# ProPrj_ESP_DigiCam.net
KiCad netlist of a schematic drawn in EasyEDA Pro
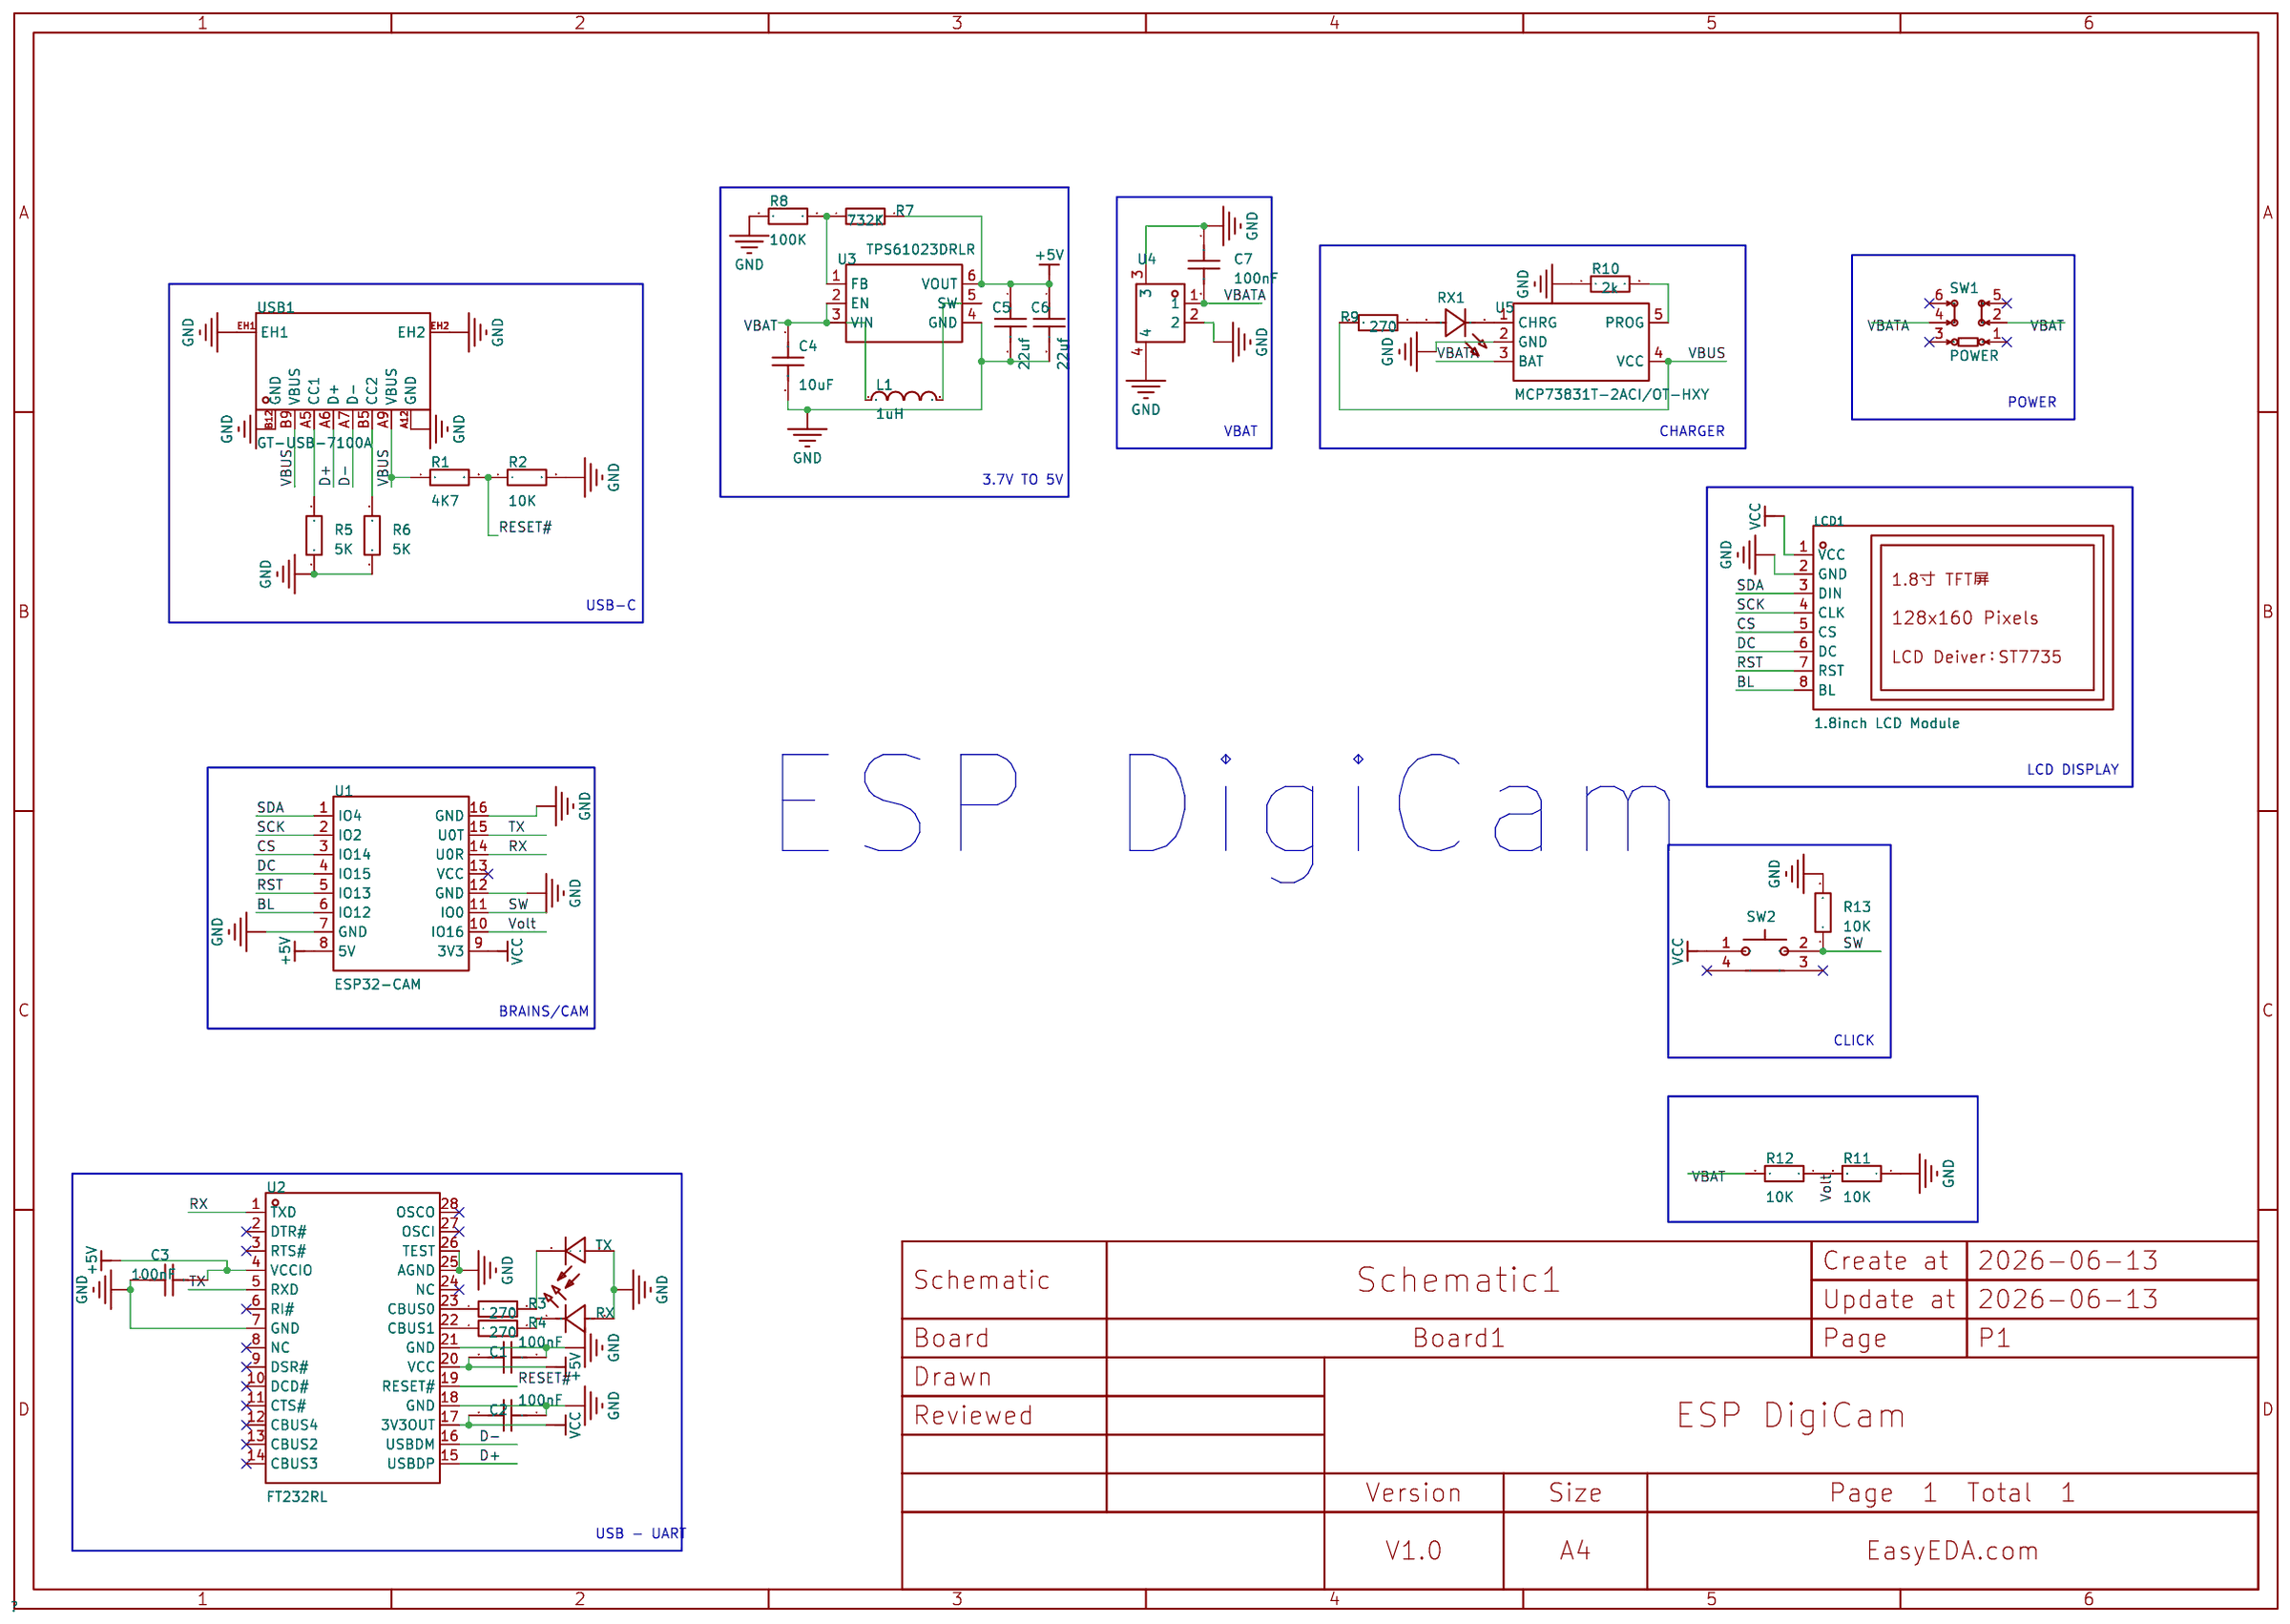
[diagram p0: schematic sheet]

(export (version "E")
  (design (tool "Eeschema 10.0.6"))
  (components
    (comp (ref "C1")
      (value "100nF")
      (footprint "easyedapro:C0603")
      (libsource (lib "easyedapro") (part "CAP"))
    )
    (comp (ref "C2")
      (value "100nF")
      (footprint "easyedapro:C0603")
      (libsource (lib "easyedapro") (part "CAP"))
    )
    (comp (ref "C3")
      (value "100nF")
      (footprint "easyedapro:C0603")
      (libsource (lib "easyedapro") (part "CAP"))
    )
    (comp (ref "C4")
      (value "10uF")
      (footprint "easyedapro:C0603")
      (libsource (lib "easyedapro") (part "CAP"))
    )
    (comp (ref "C5")
      (value "22uf")
      (footprint "easyedapro:C0603")
      (libsource (lib "easyedapro") (part "CAP"))
    )
    (comp (ref "C6")
      (value "22uf")
      (footprint "easyedapro:C0603")
      (libsource (lib "easyedapro") (part "CAP"))
    )
    (comp (ref "C7")
      (value "100nF")
      (footprint "easyedapro:C0603")
      (libsource (lib "easyedapro") (part "CAP"))
    )
    (comp (ref "L1")
      (value "1uH")
      (footprint "easyedapro:IND-SMD_L4.2-W4.2_MCW-0420")
      (fields
        (field (name "Manufacturer Part") "0420CDMCCDS-1R0MC")
        (field (name "Manufacturer") "Sumida(胜美达)")
        (field (name "Tolerance") "±20%")
      )
      (libsource (lib "easyedapro") (part "0420CDMCCDS-1R0MC"))
    )
    (comp (ref "LCD1")
      (value "1.8inch LCD Module")
      (footprint "easyedapro:LCD-TH_L56.5-W34.0_1-8INCH-LCD-MODULE")
      (fields (field (name "Manufacturer") "Waveshare(微雪电子)"))
      (libsource (lib "easyedapro") (part "1.8INCH LCD MODULE"))
    )
    (comp (ref "R1") (value "4K7") (footprint "easyedapro:R0603") (libsource (lib "easyedapro") (part "Res")))
    (comp (ref "R2") (value "10K") (footprint "easyedapro:R0603") (libsource (lib "easyedapro") (part "Res")))
    (comp (ref "R3") (value "270") (footprint "easyedapro:R0603") (libsource (lib "easyedapro") (part "Res")))
    (comp (ref "R4") (value "270") (footprint "easyedapro:R0603") (libsource (lib "easyedapro") (part "Res")))
    (comp (ref "R5") (value "5K") (footprint "easyedapro:R0603") (libsource (lib "easyedapro") (part "Res")))
    (comp (ref "R6") (value "5K") (footprint "easyedapro:R0603") (libsource (lib "easyedapro") (part "Res")))
    (comp (ref "R7")
      (value "732K")
      (footprint "easyedapro:R0603")
      (libsource (lib "easyedapro") (part "Res"))
    )
    (comp (ref "R8")
      (value "100K")
      (footprint "easyedapro:R0603")
      (libsource (lib "easyedapro") (part "Res"))
    )
    (comp (ref "R9") (value "270") (footprint "easyedapro:R0603") (libsource (lib "easyedapro") (part "Res")))
    (comp (ref "R10") (value "2k") (footprint "easyedapro:R0603") (libsource (lib "easyedapro") (part "Res")))
    (comp (ref "R11")
      (value "10K")
      (footprint "easyedapro:R0603")
      (libsource (lib "easyedapro") (part "Res"))
    )
    (comp (ref "R12")
      (value "10K")
      (footprint "easyedapro:R0603")
      (libsource (lib "easyedapro") (part "Res"))
    )
    (comp (ref "R13")
      (value "10K")
      (footprint "easyedapro:R0603")
      (libsource (lib "easyedapro") (part "Res"))
    )
    (comp (ref "RX")
      (value "YLED0603B")
      (footprint "easyedapro:LED0603-FD")
      (fields (field (name "Manufacturer") "YONGYUTAI(永裕泰)"))
      (libsource (lib "easyedapro") (part "YLED0603B"))
    )
    (comp (ref "RX1")
      (value "YLED0603B")
      (footprint "easyedapro:LED0603-FD")
      (fields (field (name "Manufacturer") "YONGYUTAI(永裕泰)"))
      (libsource (lib "easyedapro") (part "YLED0603B"))
    )
    (comp (ref "SW1")
      (value "POWER")
      (footprint "easyedapro:SW-SMD_XKB5858-W-F-75")
      (fields (field (name "Manufacturer") "XKB Connection(中国星坤)"))
      (libsource (lib "easyedapro") (part "XKB5858-W-F-75"))
    )
    (comp (ref "SW2")
      (value "1TS002G-1400-3500-CT")
      (footprint "easyedapro:KEY-SMD_1TS002G")
      (fields (field (name "Manufacturer") "HYP(鸿源精密)"))
      (libsource (lib "easyedapro") (part "1TS002G-1400-3500"))
    )
    (comp (ref "TX")
      (value "YLED0603R")
      (footprint "easyedapro:LED0603-FD")
      (fields (field (name "Manufacturer") "YONGYUTAI(永裕泰)"))
      (libsource (lib "easyedapro") (part "YLED0603R"))
    )
    (comp (ref "U1")
      (value "ESP32-CAM")
      (footprint "easyedapro:COMM-TH_16P-L40.0-W27.0-P2.54_ESP32-CAM")
      (fields (field (name "Manufacturer") "Ai-Thinker(安信可)"))
      (libsource (lib "easyedapro") (part "ESP32-CAM"))
    )
    (comp (ref "U2")
      (value "FT232RL")
      (footprint "easyedapro:SSOP-28_L10.2-W5.3-P0.65-LS7.8-BL")
      (fields (field (name "Manufacturer") "FTDI(飞特帝亚)"))
      (libsource (lib "easyedapro") (part "FT232RL"))
    )
    (comp (ref "U3")
      (value "TPS61023DRLR")
      (footprint "easyedapro:SOT-563_L1.6-W1.2-P0.50-LS1.6-BR")
      (fields (field (name "Manufacturer") "TI(德州仪器)"))
      (libsource (lib "easyedapro") (part "TPS61023DRLR"))
    )
    (comp (ref "U4")
      (value "JST Right-Angle Connector - SMD 2-Pin (Black)")
      (footprint "easyedapro:CONN-SMD_JST-PH-2-SMT-RA")
      (libsource (lib "easyedapro") (part "JST RIGHT-ANGLE CONNECTOR - SMD 2-PIN (BLACK)"))
    )
    (comp (ref "U5")
      (value "MCP73831T-2ACI/OT-HXY")
      (footprint "easyedapro:SOT-23-5_L2.9-W1.6-P0.95-LS2.8-TL")
      (fields (field (name "Manufacturer") "HXY MOSFET(华轩阳电子)"))
      (libsource (lib "easyedapro") (part "MCP73831T-2ACI/OT-HXY"))
    )
    (comp (ref "USB1")
      (value "GT-USB-7100A")
      (footprint "easyedapro:USB-C-SMD_GT-USB-7100A")
      (fields (field (name "Manufacturer") "G-Switch(品赞)"))
      (libsource (lib "easyedapro") (part "GT-USB-7100A"))
    )
  )
  (nets
    (net (code "1") (name "+5V") (class "Default")
      (node (ref "C1") (pin "2") (pinfunction "2_2") (pintype "input"))
      (node (ref "C3") (pin "2") (pinfunction "2_2") (pintype "input"))
      (node (ref "C5") (pin "1") (pinfunction "1_1") (pintype "input"))
      (node (ref "C6") (pin "1") (pinfunction "1_1") (pintype "input"))
      (node (ref "R7") (pin "2") (pinfunction "2_2") (pintype "input"))
      (node (ref "U1") (pin "8") (pinfunction "5V_8") (pintype "unspecified"))
      (node (ref "U2") (pin "20") (pinfunction "VCC_20") (pintype "unspecified"))
      (node (ref "U2") (pin "4") (pinfunction "VCCIO_4") (pintype "unspecified"))
      (node (ref "U3") (pin "6") (pinfunction "VOUT_6") (pintype "unspecified"))
    )
    (net (code "2") (name "/BL") (class "Default")
      (node (ref "LCD1") (pin "8") (pinfunction "BL_8") (pintype "input"))
      (node (ref "U1") (pin "6") (pinfunction "IO12_6") (pintype "unspecified"))
    )
    (net (code "3") (name "/CS") (class "Default")
      (node (ref "LCD1") (pin "5") (pinfunction "CS_5") (pintype "input"))
      (node (ref "U1") (pin "3") (pinfunction "IO14_3") (pintype "unspecified"))
    )
    (net (code "4") (name "/D+") (class "Default")
      (node (ref "U2") (pin "15") (pinfunction "USBDP_15") (pintype "unspecified"))
      (node (ref "USB1") (pin "A6") (pinfunction "D+_A6") (pintype "unspecified"))
    )
    (net (code "5") (name "/D-") (class "Default")
      (node (ref "U2") (pin "16") (pinfunction "USBDM_16") (pintype "unspecified"))
      (node (ref "USB1") (pin "A7") (pinfunction "D-_A7") (pintype "unspecified"))
    )
    (net (code "6") (name "/DC") (class "Default")
      (node (ref "LCD1") (pin "6") (pinfunction "DC_6") (pintype "input"))
      (node (ref "U1") (pin "4") (pinfunction "IO15_4") (pintype "unspecified"))
    )
    (net (code "7") (name "/RESET#") (class "Default")
      (node (ref "R1") (pin "2") (pinfunction "2_2") (pintype "input"))
      (node (ref "R2") (pin "1") (pinfunction "1_1") (pintype "input"))
      (node (ref "U2") (pin "19") (pinfunction "RESET#_19") (pintype "unspecified"))
    )
    (net (code "8") (name "/RST") (class "Default")
      (node (ref "LCD1") (pin "7") (pinfunction "RST_7") (pintype "input"))
      (node (ref "U1") (pin "5") (pinfunction "IO13_5") (pintype "unspecified"))
    )
    (net (code "9") (name "/RX") (class "Default")
      (node (ref "U1") (pin "14") (pinfunction "U0R_14") (pintype "unspecified"))
      (node (ref "U2") (pin "1") (pinfunction "TXD_1") (pintype "unspecified"))
    )
    (net (code "10") (name "/SCK") (class "Default")
      (node (ref "LCD1") (pin "4") (pinfunction "CLK_4") (pintype "input"))
      (node (ref "U1") (pin "2") (pinfunction "IO2_2") (pintype "unspecified"))
    )
    (net (code "11") (name "/SDA") (class "Default")
      (node (ref "LCD1") (pin "3") (pinfunction "DIN_3") (pintype "input"))
      (node (ref "U1") (pin "1") (pinfunction "IO4_1") (pintype "unspecified"))
    )
    (net (code "12") (name "/SW") (class "Default")
      (node (ref "R13") (pin "1") (pinfunction "1_1") (pintype "input"))
      (node (ref "SW2") (pin "2") (pinfunction "2_2") (pintype "input"))
      (node (ref "U1") (pin "11") (pinfunction "IO0_11") (pintype "unspecified"))
    )
    (net (code "13") (name "/TX") (class "Default")
      (node (ref "U1") (pin "15") (pinfunction "U0T_15") (pintype "unspecified"))
      (node (ref "U2") (pin "5") (pinfunction "RXD_5") (pintype "unspecified"))
    )
    (net (code "14") (name "/VBAT") (class "Default")
      (node (ref "C4") (pin "1") (pinfunction "1_1") (pintype "input"))
      (node (ref "L1") (pin "1") (pinfunction "1_1") (pintype "input"))
      (node (ref "R12") (pin "2") (pinfunction "2_2") (pintype "input"))
      (node (ref "SW1") (pin "2") (pinfunction "2_2") (pintype "unspecified"))
      (node (ref "U3") (pin "2") (pinfunction "EN_2") (pintype "unspecified"))
      (node (ref "U3") (pin "3") (pinfunction "VIN_3") (pintype "unspecified"))
    )
    (net (code "15") (name "/VBATA") (class "Default")
      (node (ref "C7") (pin "2") (pinfunction "2_2") (pintype "input"))
      (node (ref "SW1") (pin "4") (pinfunction "4_4") (pintype "unspecified"))
      (node (ref "U4") (pin "1") (pinfunction "1_1") (pintype "unspecified"))
      (node (ref "U5") (pin "3") (pinfunction "BAT_3") (pintype "unspecified"))
    )
    (net (code "16") (name "/VBUS") (class "Default")
      (node (ref "R1") (pin "1") (pinfunction "1_1") (pintype "input"))
      (node (ref "R9") (pin "1") (pinfunction "1_1") (pintype "input"))
      (node (ref "U5") (pin "4") (pinfunction "VCC_4") (pintype "unspecified"))
      (node (ref "USB1") (pin "A9") (pinfunction "VBUS_A9") (pintype "unspecified"))
      (node (ref "USB1") (pin "B9") (pinfunction "VBUS_B9") (pintype "unspecified"))
    )
    (net (code "17") (name "/Volt") (class "Default")
      (node (ref "R11") (pin "2") (pinfunction "2_2") (pintype "input"))
      (node (ref "R12") (pin "1") (pinfunction "1_1") (pintype "input"))
      (node (ref "U1") (pin "10") (pinfunction "IO16_10") (pintype "unspecified"))
    )
    (net (code "18") (name "GND") (class "Default")
      (node (ref "C1") (pin "1") (pinfunction "1_1") (pintype "input"))
      (node (ref "C2") (pin "1") (pinfunction "1_1") (pintype "input"))
      (node (ref "C3") (pin "1") (pinfunction "1_1") (pintype "input"))
      (node (ref "C4") (pin "2") (pinfunction "2_2") (pintype "input"))
      (node (ref "C5") (pin "2") (pinfunction "2_2") (pintype "input"))
      (node (ref "C6") (pin "2") (pinfunction "2_2") (pintype "input"))
      (node (ref "C7") (pin "1") (pinfunction "1_1") (pintype "input"))
      (node (ref "LCD1") (pin "2") (pinfunction "GND_2") (pintype "input"))
      (node (ref "R10") (pin "1") (pinfunction "1_1") (pintype "input"))
      (node (ref "R11") (pin "1") (pinfunction "1_1") (pintype "input"))
      (node (ref "R13") (pin "2") (pinfunction "2_2") (pintype "input"))
      (node (ref "R2") (pin "2") (pinfunction "2_2") (pintype "input"))
      (node (ref "R5") (pin "1") (pinfunction "1_1") (pintype "input"))
      (node (ref "R6") (pin "1") (pinfunction "1_1") (pintype "input"))
      (node (ref "R8") (pin "2") (pinfunction "2_2") (pintype "input"))
      (node (ref "RX") (pin "2") (pinfunction "A_2") (pintype "unspecified"))
      (node (ref "TX") (pin "1") (pinfunction "+_1") (pintype "unspecified"))
      (node (ref "U1") (pin "12") (pinfunction "GND_12") (pintype "unspecified"))
      (node (ref "U1") (pin "16") (pinfunction "GND_16") (pintype "unspecified"))
      (node (ref "U1") (pin "7") (pinfunction "GND_7") (pintype "unspecified"))
      (node (ref "U2") (pin "18") (pinfunction "GND_18") (pintype "unspecified"))
      (node (ref "U2") (pin "21") (pinfunction "GND_21") (pintype "unspecified"))
      (node (ref "U2") (pin "25") (pinfunction "AGND_25") (pintype "unspecified"))
      (node (ref "U2") (pin "26") (pinfunction "TEST_26") (pintype "unspecified"))
      (node (ref "U2") (pin "7") (pinfunction "GND_7") (pintype "unspecified"))
      (node (ref "U3") (pin "4") (pinfunction "GND_4") (pintype "unspecified"))
      (node (ref "U4") (pin "2") (pinfunction "2_2") (pintype "unspecified"))
      (node (ref "U4") (pin "3") (pinfunction "3_3") (pintype "unspecified"))
      (node (ref "U4") (pin "4") (pinfunction "4_4") (pintype "unspecified"))
      (node (ref "U5") (pin "2") (pinfunction "GND_2") (pintype "unspecified"))
      (node (ref "USB1") (pin "A12") (pinfunction "GND_A12") (pintype "unspecified"))
      (node (ref "USB1") (pin "B12") (pinfunction "GND_B12") (pintype "unspecified"))
      (node (ref "USB1") (pin "EH1") (pinfunction "EH1_EH1") (pintype "unspecified"))
      (node (ref "USB1") (pin "EH2") (pinfunction "EH2_EH2") (pintype "unspecified"))
    )
    (net (code "19") (name "Net-(RX-K)") (class "Default")
      (node (ref "R4") (pin "2") (pinfunction "2_2") (pintype "input"))
      (node (ref "RX") (pin "1") (pinfunction "K_1") (pintype "unspecified"))
    )
    (net (code "20") (name "Net-(RX1-A)") (class "Default")
      (node (ref "R9") (pin "2") (pinfunction "2_2") (pintype "input"))
      (node (ref "RX1") (pin "2") (pinfunction "A_2") (pintype "unspecified"))
    )
    (net (code "21") (name "Net-(RX1-K)") (class "Default")
      (node (ref "RX1") (pin "1") (pinfunction "K_1") (pintype "unspecified"))
      (node (ref "U5") (pin "1") (pinfunction "CHRG_1") (pintype "unspecified"))
    )
    (net (code "22") (name "Net-(TX--)") (class "Default")
      (node (ref "R3") (pin "2") (pinfunction "2_2") (pintype "input"))
      (node (ref "TX") (pin "2") (pinfunction "-_2") (pintype "unspecified"))
    )
    (net (code "23") (name "Net-(U2-CBUS0)") (class "Default")
      (node (ref "R3") (pin "1") (pinfunction "1_1") (pintype "input"))
      (node (ref "U2") (pin "23") (pinfunction "CBUS0_23") (pintype "unspecified"))
    )
    (net (code "24") (name "Net-(U2-CBUS1)") (class "Default")
      (node (ref "R4") (pin "1") (pinfunction "1_1") (pintype "input"))
      (node (ref "U2") (pin "22") (pinfunction "CBUS1_22") (pintype "unspecified"))
    )
    (net (code "25") (name "Net-(U3-FB)") (class "Default")
      (node (ref "R7") (pin "1") (pinfunction "1_1") (pintype "input"))
      (node (ref "R8") (pin "1") (pinfunction "1_1") (pintype "input"))
      (node (ref "U3") (pin "1") (pinfunction "FB_1") (pintype "unspecified"))
    )
    (net (code "26") (name "Net-(U3-SW)") (class "Default")
      (node (ref "L1") (pin "2") (pinfunction "2_2") (pintype "input"))
      (node (ref "U3") (pin "5") (pinfunction "SW_5") (pintype "unspecified"))
    )
    (net (code "27") (name "Net-(U5-PROG)") (class "Default")
      (node (ref "R10") (pin "2") (pinfunction "2_2") (pintype "input"))
      (node (ref "U5") (pin "5") (pinfunction "PROG_5") (pintype "unspecified"))
    )
    (net (code "28") (name "Net-(USB1-CC1)") (class "Default")
      (node (ref "R5") (pin "2") (pinfunction "2_2") (pintype "input"))
      (node (ref "USB1") (pin "A5") (pinfunction "CC1_A5") (pintype "unspecified"))
    )
    (net (code "29") (name "Net-(USB1-CC2)") (class "Default")
      (node (ref "R6") (pin "2") (pinfunction "2_2") (pintype "input"))
      (node (ref "USB1") (pin "B5") (pinfunction "CC2_B5") (pintype "unspecified"))
    )
    (net (code "30") (name "VCC") (class "Default")
      (node (ref "C2") (pin "2") (pinfunction "2_2") (pintype "input"))
      (node (ref "LCD1") (pin "1") (pinfunction "VCC_1") (pintype "input"))
      (node (ref "SW2") (pin "1") (pinfunction "1_1") (pintype "input"))
      (node (ref "U1") (pin "9") (pinfunction "3V3_9") (pintype "unspecified"))
      (node (ref "U2") (pin "17") (pinfunction "3V3OUT_17") (pintype "unspecified"))
    )
    (net (code "31") (name "unconnected-(SW1-Pad1)") (class "Default")
      (node (ref "SW1") (pin "1") (pinfunction "1_1") (pintype "unspecified+no_connect"))
    )
    (net (code "32") (name "unconnected-(SW1-Pad3)") (class "Default")
      (node (ref "SW1") (pin "3") (pinfunction "3_3") (pintype "unspecified+no_connect"))
    )
    (net (code "33") (name "unconnected-(SW1-Pad5)") (class "Default")
      (node (ref "SW1") (pin "5") (pinfunction "5_5") (pintype "unspecified+no_connect"))
    )
    (net (code "34") (name "unconnected-(SW1-Pad6)") (class "Default")
      (node (ref "SW1") (pin "6") (pinfunction "6_6") (pintype "unspecified+no_connect"))
    )
    (net (code "35") (name "unconnected-(SW2-Pad3)") (class "Default")
      (node (ref "SW2") (pin "3") (pinfunction "3_3") (pintype "input+no_connect"))
    )
    (net (code "36") (name "unconnected-(SW2-Pad4)") (class "Default")
      (node (ref "SW2") (pin "4") (pinfunction "4_4") (pintype "input+no_connect"))
    )
    (net (code "37") (name "unconnected-(U1-VCC-Pad13)") (class "Default")
      (node (ref "U1") (pin "13") (pinfunction "VCC_13") (pintype "unspecified+no_connect"))
    )
    (net (code "38") (name "unconnected-(U2-CBUS2-Pad13)") (class "Default")
      (node (ref "U2") (pin "13") (pinfunction "CBUS2_13") (pintype "unspecified+no_connect"))
    )
    (net (code "39") (name "unconnected-(U2-CBUS3-Pad14)") (class "Default")
      (node (ref "U2") (pin "14") (pinfunction "CBUS3_14") (pintype "unspecified+no_connect"))
    )
    (net (code "40") (name "unconnected-(U2-CBUS4-Pad12)") (class "Default")
      (node (ref "U2") (pin "12") (pinfunction "CBUS4_12") (pintype "unspecified+no_connect"))
    )
    (net (code "41") (name "unconnected-(U2-CTS#-Pad11)") (class "Default")
      (node (ref "U2") (pin "11") (pinfunction "CTS#_11") (pintype "unspecified+no_connect"))
    )
    (net (code "42") (name "unconnected-(U2-DCD#-Pad10)") (class "Default")
      (node (ref "U2") (pin "10") (pinfunction "DCD#_10") (pintype "unspecified+no_connect"))
    )
    (net (code "43") (name "unconnected-(U2-DSR#-Pad9)") (class "Default")
      (node (ref "U2") (pin "9") (pinfunction "DSR#_9") (pintype "unspecified+no_connect"))
    )
    (net (code "44") (name "unconnected-(U2-DTR#-Pad2)") (class "Default")
      (node (ref "U2") (pin "2") (pinfunction "DTR#_2") (pintype "unspecified+no_connect"))
    )
    (net (code "45") (name "unconnected-(U2-NC-Pad8)") (class "Default")
      (node (ref "U2") (pin "8") (pinfunction "NC_8") (pintype "unspecified+no_connect"))
    )
    (net (code "46") (name "unconnected-(U2-NC-Pad24)") (class "Default")
      (node (ref "U2") (pin "24") (pinfunction "NC_24") (pintype "unspecified+no_connect"))
    )
    (net (code "47") (name "unconnected-(U2-OSCI-Pad27)") (class "Default")
      (node (ref "U2") (pin "27") (pinfunction "OSCI_27") (pintype "unspecified+no_connect"))
    )
    (net (code "48") (name "unconnected-(U2-OSCO-Pad28)") (class "Default")
      (node (ref "U2") (pin "28") (pinfunction "OSCO_28") (pintype "unspecified+no_connect"))
    )
    (net (code "49") (name "unconnected-(U2-RI#-Pad6)") (class "Default")
      (node (ref "U2") (pin "6") (pinfunction "RI#_6") (pintype "unspecified+no_connect"))
    )
    (net (code "50") (name "unconnected-(U2-RTS#-Pad3)") (class "Default")
      (node (ref "U2") (pin "3") (pinfunction "RTS#_3") (pintype "unspecified+no_connect"))
    )
  )
)
